# LB_BIT_p2_COINBATTERY-v03_rev3.net
KiCad netlist of a schematic drawn in EAGLE
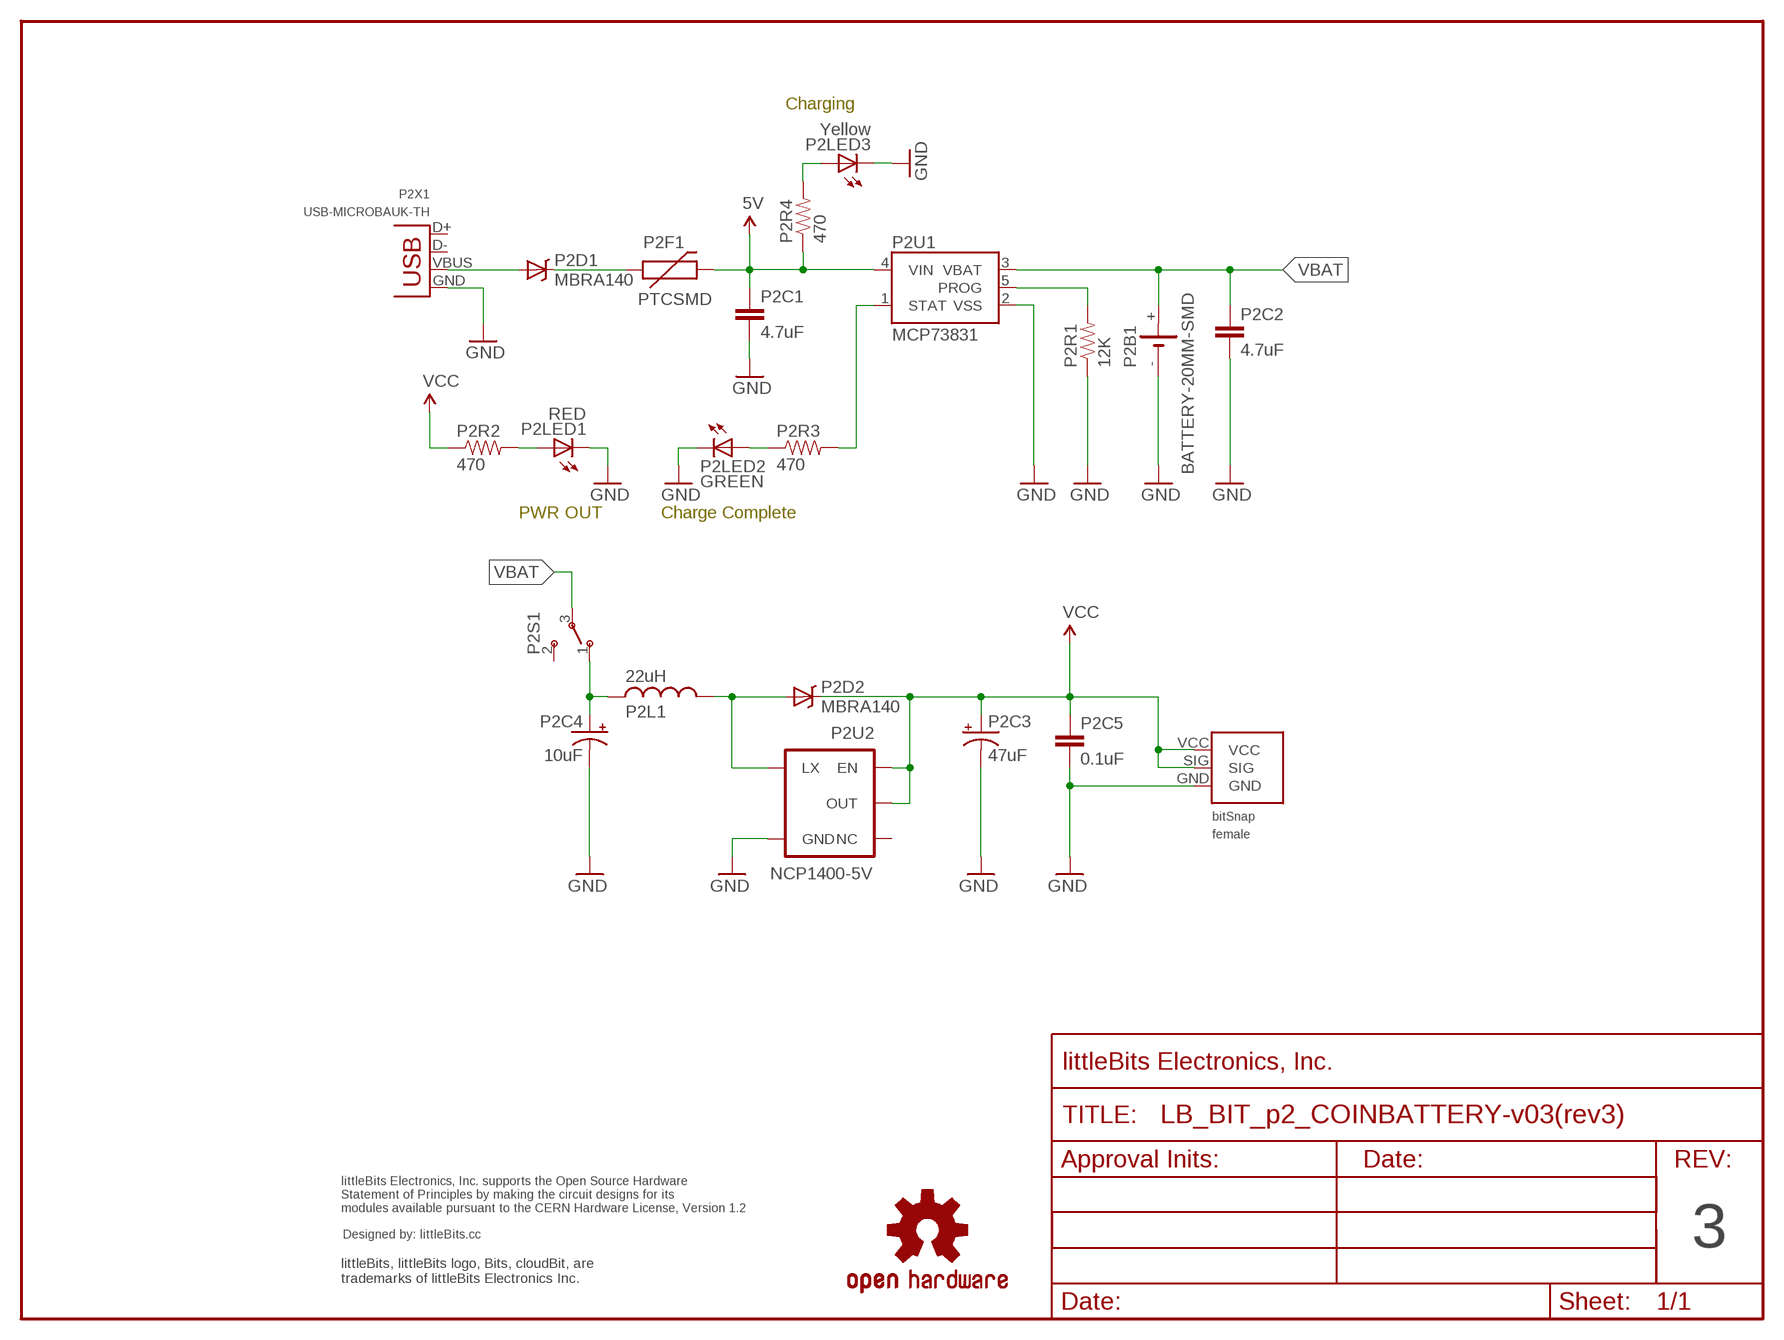
[diagram p0: schematic, sheet 1]

(export (version "E")
  (design (tool "Eeschema 10.0.6"))
  (components
    (comp (ref "P2B1")
      (value "BATTERY-20MM-SMD")
      (footprint "eagle-import:BATTERY_WELDTABS-20MM-SMD")
      (libsource (lib "eagle-import") (part "BATTERY-20MM-SMD"))
    )
    (comp (ref "P2BSF1")
      (value "BITSNAP_V03_FEMALE")
      (footprint "eagle-import:BITSNAP_V03_FEMALE")
      (libsource (lib "eagle-import") (part "BITSNAP_V03_FEMALE"))
    )
    (comp (ref "P2C1")
      (value "4.7uF")
      (footprint "eagle-import:0603-CAP")
      (libsource (lib "eagle-import") (part "CAP0603-CAP"))
    )
    (comp (ref "P2C2")
      (value "4.7uF")
      (footprint "eagle-import:0603-CAP")
      (libsource (lib "eagle-import") (part "CAP0603-CAP"))
    )
    (comp (ref "P2C3")
      (value "47uF")
      (footprint "eagle-import:EIA3528")
      (libsource (lib "eagle-import") (part "CAP_POL3528"))
    )
    (comp (ref "P2C4")
      (value "10uF")
      (footprint "eagle-import:EIA3216")
      (libsource (lib "eagle-import") (part "CAP_POL1206"))
    )
    (comp (ref "P2C5")
      (value "0.1uF")
      (footprint "eagle-import:0603-CAP")
      (libsource (lib "eagle-import") (part "CAP0603-CAP"))
    )
    (comp (ref "P2D1")
      (value "MBRA140")
      (footprint "eagle-import:SMA-DIODE")
      (libsource (lib "eagle-import") (part "DIODE-SCHOTTKY_"))
    )
    (comp (ref "P2D2")
      (value "MBRA140")
      (footprint "eagle-import:SMA-DIODE")
      (libsource (lib "eagle-import") (part "DIODE-SCHOTTKY_"))
    )
    (comp (ref "P2F1")
      (value "PTCSMD")
      (footprint "eagle-import:PTC-1206")
      (libsource (lib "eagle-import") (part "PTCSMD"))
    )
    (comp (ref "P2L1")
      (value "22uH")
      (footprint "eagle-import:INDUCTOR-TAITO_YUDEN_NR6028T220M")
      (libsource (lib "eagle-import") (part "INDUCTOR-TAITO_YUDEN_NR6028T220M"))
    )
    (comp (ref "P2LED1")
      (value "RED")
      (footprint "eagle-import:LED-1206")
      (libsource (lib "eagle-import") (part "LED1206"))
    )
    (comp (ref "P2LED2")
      (value "GREEN")
      (footprint "eagle-import:LED-1206")
      (libsource (lib "eagle-import") (part "LED1206"))
    )
    (comp (ref "P2LED3")
      (value "Yellow")
      (footprint "eagle-import:LED-1206")
      (libsource (lib "eagle-import") (part "LED1206"))
    )
    (comp (ref "P2R1")
      (value "12K")
      (footprint "eagle-import:0603-RES")
      (libsource (lib "eagle-import") (part "RESISTOR0603-RES"))
    )
    (comp (ref "P2R2")
      (value "470")
      (footprint "eagle-import:0603-RES")
      (libsource (lib "eagle-import") (part "RESISTOR0603-RES"))
    )
    (comp (ref "P2R3")
      (value "470")
      (footprint "eagle-import:0603-RES")
      (libsource (lib "eagle-import") (part "RESISTOR0603-RES"))
    )
    (comp (ref "P2R4")
      (value "470")
      (footprint "eagle-import:0603-RES")
      (libsource (lib "eagle-import") (part "RESISTOR0603-RES"))
    )
    (comp (ref "P2S1")
      (value "SWITCH-SMD-SLIDE-CSS1210TB")
      (footprint "eagle-import:COPAL_CSS1210TB")
      (libsource (lib "eagle-import") (part "SWITCH-SMD-SLIDE-CSS1210TB"))
    )
    (comp (ref "P2U1")
      (value "MCP73831")
      (footprint "eagle-import:SOT23-5")
      (libsource (lib "eagle-import") (part "MCP73831"))
    )
    (comp (ref "P2U2")
      (value "NCP1400-5V")
      (footprint "eagle-import:SOT23-5")
      (libsource (lib "eagle-import") (part "V_REG_NCP1400SOT23-5"))
    )
    (comp (ref "P2X1")
      (value "USB-MICROBAUK-TH")
      (footprint "eagle-import:USB-MICROB-AUK")
      (libsource (lib "eagle-import") (part "USB-MICROBAUK-TH"))
    )
    (comp (ref "U$3")
      (value "OSHWCREDIT")
      (footprint "eagle-import:OSHWCREDIT")
      (libsource (lib "eagle-import") (part "OSHWCREDIT"))
    )
    (comp (ref "U$4")
      (value "OSHW-LOGOL")
      (footprint "eagle-import:OSHW-LOGO-L")
      (libsource (lib "eagle-import") (part "OSHW-LOGOL"))
    )
    (comp (ref "U$6")
      (value "FRAME-LETTER-OHWOHW")
      (footprint "eagle-import:FABDWG01-OHW")
      (libsource (lib "eagle-import") (part "FRAME-LETTER-OHWOHW"))
    )
  )
  (nets
    (net (code "1") (name "5V") (class "Default")
      (node (ref "P2C1") (pin "1") (pinfunction "1_1") (pintype "passive"))
      (node (ref "P2F1") (pin "2") (pinfunction "2_2") (pintype "bidirectional"))
      (node (ref "P2R4") (pin "1") (pinfunction "1_1") (pintype "passive"))
      (node (ref "P2U1") (pin "4") (pinfunction "VIN_4") (pintype "power_in"))
    )
    (net (code "2") (name "GND") (class "Default")
      (node (ref "P2B1") (pin "-") (pinfunction "-_-") (pintype "power_in"))
      (node (ref "P2BSF1") (pin "GND") (pinfunction "GND_GND") (pintype "bidirectional"))
      (node (ref "P2C1") (pin "2") (pinfunction "2_2") (pintype "passive"))
      (node (ref "P2C2") (pin "2") (pinfunction "2_2") (pintype "passive"))
      (node (ref "P2C3") (pin "C") (pinfunction "-_C") (pintype "passive"))
      (node (ref "P2C4") (pin "C") (pinfunction "-_C") (pintype "passive"))
      (node (ref "P2C5") (pin "2") (pinfunction "2_2") (pintype "passive"))
      (node (ref "P2LED1") (pin "C") (pinfunction "C_C") (pintype "passive"))
      (node (ref "P2LED2") (pin "C") (pinfunction "C_C") (pintype "passive"))
      (node (ref "P2LED3") (pin "C") (pinfunction "C_C") (pintype "passive"))
      (node (ref "P2R1") (pin "1") (pinfunction "1_1") (pintype "passive"))
      (node (ref "P2U1") (pin "2") (pinfunction "VSS_2") (pintype "power_in"))
      (node (ref "P2U2") (pin "4") (pinfunction "GND_4") (pintype "input"))
      (node (ref "P2X1") (pin "GND") (pinfunction "GND_GND") (pintype "bidirectional"))
    )
    (net (code "3") (name "Net-(P2C4-+)") (class "Default")
      (node (ref "P2C4") (pin "A") (pinfunction "+_A") (pintype "passive"))
      (node (ref "P2L1") (pin "P$2") (pinfunction "2_P$2") (pintype "passive"))
      (node (ref "P2S1") (pin "1") (pinfunction "1_1") (pintype "passive"))
    )
    (net (code "4") (name "Net-(P2D1-PadA)") (class "Default")
      (node (ref "P2D1") (pin "A") (pinfunction "A_A") (pintype "passive"))
      (node (ref "P2X1") (pin "VBUS") (pinfunction "VBUS_VBUS") (pintype "bidirectional"))
    )
    (net (code "5") (name "Net-(P2D1-PadC)") (class "Default")
      (node (ref "P2D1") (pin "C") (pinfunction "C_C") (pintype "passive"))
      (node (ref "P2F1") (pin "1") (pinfunction "1_1") (pintype "bidirectional"))
    )
    (net (code "6") (name "Net-(P2L1-1)") (class "Default")
      (node (ref "P2D2") (pin "A") (pinfunction "A_A") (pintype "passive"))
      (node (ref "P2L1") (pin "P$1") (pinfunction "1_P$1") (pintype "passive"))
      (node (ref "P2U2") (pin "5") (pinfunction "LX_5") (pintype "input"))
    )
    (net (code "7") (name "Net-(P2LED1-PadA)") (class "Default")
      (node (ref "P2LED1") (pin "A") (pinfunction "A_A") (pintype "passive"))
      (node (ref "P2R2") (pin "2") (pinfunction "2_2") (pintype "passive"))
    )
    (net (code "8") (name "Net-(P2LED2-PadA)") (class "Default")
      (node (ref "P2LED2") (pin "A") (pinfunction "A_A") (pintype "passive"))
      (node (ref "P2R3") (pin "1") (pinfunction "1_1") (pintype "passive"))
    )
    (net (code "9") (name "Net-(P2LED3-PadA)") (class "Default")
      (node (ref "P2LED3") (pin "A") (pinfunction "A_A") (pintype "passive"))
      (node (ref "P2R4") (pin "2") (pinfunction "2_2") (pintype "passive"))
    )
    (net (code "10") (name "Net-(P2U1-PROG)") (class "Default")
      (node (ref "P2R1") (pin "2") (pinfunction "2_2") (pintype "passive"))
      (node (ref "P2U1") (pin "5") (pinfunction "PROG_5") (pintype "input"))
    )
    (net (code "11") (name "Net-(P2U1-STAT)") (class "Default")
      (node (ref "P2R3") (pin "2") (pinfunction "2_2") (pintype "passive"))
      (node (ref "P2U1") (pin "1") (pinfunction "STAT_1") (pintype "output"))
    )
    (net (code "12") (name "VBAT") (class "Default")
      (node (ref "P2B1") (pin "+") (pinfunction "+_+") (pintype "power_in"))
      (node (ref "P2C2") (pin "1") (pinfunction "1_1") (pintype "passive"))
      (node (ref "P2S1") (pin "3") (pinfunction "3_3") (pintype "passive"))
      (node (ref "P2U1") (pin "3") (pinfunction "VBAT_3") (pintype "power_in"))
    )
    (net (code "13") (name "VCC") (class "Default")
      (node (ref "P2BSF1") (pin "SIG") (pinfunction "SIG_SIG") (pintype "bidirectional"))
      (node (ref "P2BSF1") (pin "VCC") (pinfunction "VCC_VCC") (pintype "bidirectional"))
      (node (ref "P2C3") (pin "A") (pinfunction "+_A") (pintype "passive"))
      (node (ref "P2C5") (pin "1") (pinfunction "1_1") (pintype "passive"))
      (node (ref "P2D2") (pin "C") (pinfunction "C_C") (pintype "passive"))
      (node (ref "P2R2") (pin "1") (pinfunction "1_1") (pintype "passive"))
      (node (ref "P2U2") (pin "1") (pinfunction "EN_1") (pintype "input"))
      (node (ref "P2U2") (pin "2") (pinfunction "OUT_2") (pintype "passive"))
    )
    (net (code "14") (name "unconnected-(P2S1-Pad2)") (class "Default")
      (node (ref "P2S1") (pin "2") (pinfunction "2_2") (pintype "passive"))
    )
    (net (code "15") (name "unconnected-(P2U2-NC-Pad3)") (class "Default")
      (node (ref "P2U2") (pin "3") (pinfunction "NC_3") (pintype "input"))
    )
    (net (code "16") (name "unconnected-(P2X1-PadD+)") (class "Default")
      (node (ref "P2X1") (pin "D+") (pinfunction "D+_D+") (pintype "bidirectional"))
    )
    (net (code "17") (name "unconnected-(P2X1-PadD-)") (class "Default")
      (node (ref "P2X1") (pin "D-") (pinfunction "D-_D-") (pintype "bidirectional"))
    )
  )
)
